# tissuetesterrev3.net
KiCad netlist of a schematic drawn in EAGLE
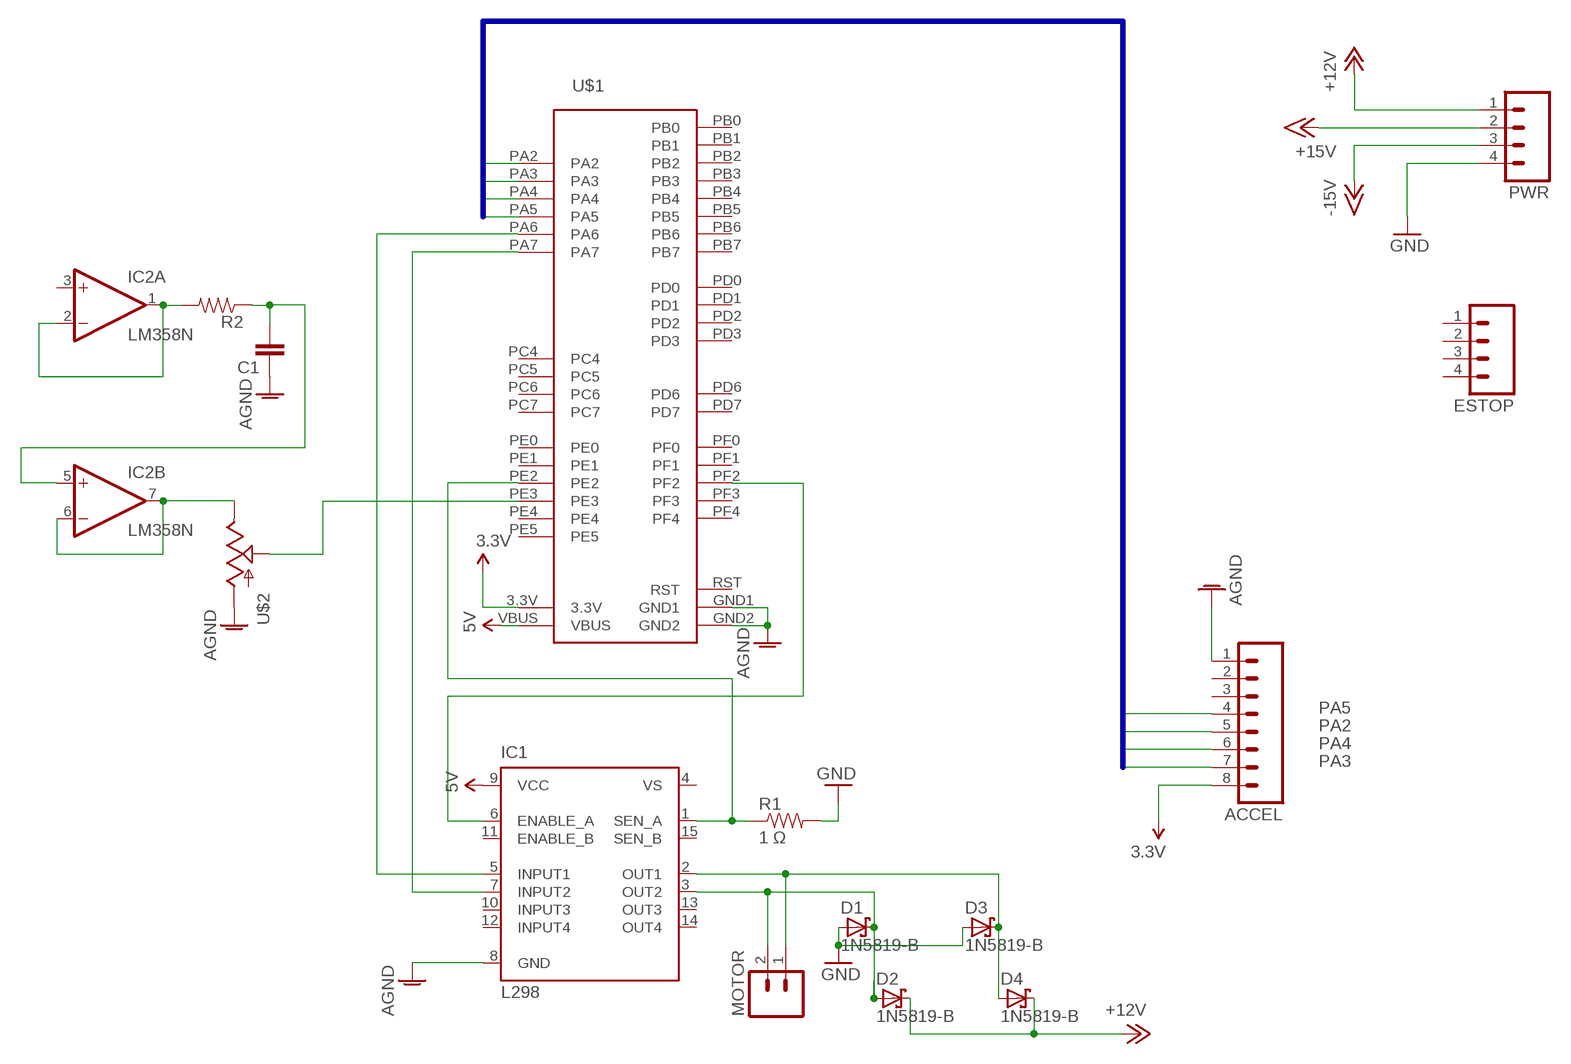
[diagram p0: schematic, sheet 1]

(export (version "E")
  (design (tool "Eeschema 10.0.6"))
  (components
    (comp (ref "ACCEL")
      (value "M08LOCK")
      (footprint "eagle-import:1X08_LOCK")
      (libsource (lib "eagle-import") (part "M08LOCK"))
    )
    (comp (ref "C1")
      (value "CAPKIT")
      (footprint "eagle-import:CAP-PTH-SMALL-KIT")
      (libsource (lib "eagle-import") (part "CAPKIT"))
    )
    (comp (ref "D1")
      (value "1N5819-B")
      (footprint "eagle-import:DO41-7.6")
      (libsource (lib "eagle-import") (part "1N5819-B"))
    )
    (comp (ref "D2")
      (value "1N5819-B")
      (footprint "eagle-import:DO41-7.6")
      (libsource (lib "eagle-import") (part "1N5819-B"))
    )
    (comp (ref "D3")
      (value "1N5819-B")
      (footprint "eagle-import:DO41-7.6")
      (libsource (lib "eagle-import") (part "1N5819-B"))
    )
    (comp (ref "D4")
      (value "1N5819-B")
      (footprint "eagle-import:DO41-7.6")
      (libsource (lib "eagle-import") (part "1N5819-B"))
    )
    (comp (ref "ESTOP")
      (value "M04LOCK")
      (footprint "eagle-import:1X04_LOCK")
      (libsource (lib "eagle-import") (part "M04LOCK"))
    )
    (comp (ref "IC1")
      (value "L298")
      (footprint "eagle-import:MULTIWATT-15")
      (fields (field (name "MPN") "L298N"))
      (libsource (lib "eagle-import") (part "L298"))
    )
    (comp (ref "IC2")
      (value "LM358N")
      (footprint "eagle-import:DIL08")
      (libsource (lib "eagle-import") (part "LM358N"))
    )
    (comp (ref "MOTOR")
      (value "M023.5MM")
      (footprint "eagle-import:SCREWTERMINAL-3.5MM-2")
      (libsource (lib "eagle-import") (part "M023.5MM"))
    )
    (comp (ref "PWR")
      (value "M04SCREW")
      (footprint "eagle-import:SCREWTERMINAL-3.5MM-4")
      (libsource (lib "eagle-import") (part "M04SCREW"))
    )
    (comp (ref "R1")
      (value "1 Ω")
      (footprint "eagle-import:AXIAL-0.6")
      (libsource (lib "eagle-import") (part "RESISTORPTH-1W"))
    )
    (comp (ref "R2")
      (value "RESISTORKIT")
      (footprint "eagle-import:AXIAL-0.3-KIT")
      (libsource (lib "eagle-import") (part "SparkFun-Resistors_RESISTORKIT"))
    )
    (comp (ref "U$1")
      (value "STELLARIS-LAUNCHPADSTELLARIS-LAUNCHPAD")
      (footprint "eagle-import:LAUNCHPAD-XL")
      (libsource (lib "eagle-import") (part "STELLARIS-LAUNCHPADSTELLARIS-LAUNCHPAD"))
    )
    (comp (ref "U$2")
      (value "POT")
      (footprint "eagle-import:ALPS_POT")
      (libsource (lib "eagle-import") (part "POT"))
    )
  )
  (nets
    (net (code "1") (name "+12V") (class "Default")
      (node (ref "D2") (pin "C") (pinfunction "C_C") (pintype "passive"))
      (node (ref "D4") (pin "C") (pinfunction "C_C") (pintype "passive"))
      (node (ref "PWR") (pin "1") (pinfunction "1_1") (pintype "passive"))
    )
    (net (code "2") (name "+15V") (class "Default")
      (node (ref "PWR") (pin "2") (pinfunction "2_2") (pintype "passive"))
    )
    (net (code "3") (name "-15V") (class "Default")
      (node (ref "PWR") (pin "3") (pinfunction "3_3") (pintype "passive"))
    )
    (net (code "4") (name "/PA2") (class "Default")
      (node (ref "ACCEL") (pin "5") (pinfunction "5_5") (pintype "passive"))
      (node (ref "U$1") (pin "PA2") (pinfunction "PA2_PA2") (pintype "bidirectional"))
    )
    (net (code "5") (name "/PA3") (class "Default")
      (node (ref "ACCEL") (pin "7") (pinfunction "7_7") (pintype "passive"))
      (node (ref "U$1") (pin "PA3") (pinfunction "PA3_PA3") (pintype "bidirectional"))
    )
    (net (code "6") (name "/PA4") (class "Default")
      (node (ref "ACCEL") (pin "6") (pinfunction "6_6") (pintype "passive"))
      (node (ref "U$1") (pin "PA4") (pinfunction "PA4_PA4") (pintype "bidirectional"))
    )
    (net (code "7") (name "/PA5") (class "Default")
      (node (ref "ACCEL") (pin "4") (pinfunction "4_4") (pintype "passive"))
      (node (ref "U$1") (pin "PA5") (pinfunction "PA5_PA5") (pintype "bidirectional"))
    )
    (net (code "8") (name "/RST") (class "Default")
      (node (ref "U$1") (pin "RST") (pinfunction "RST_RST") (pintype "power_in"))
    )
    (net (code "9") (name "/VS") (class "Default")
      (node (ref "IC1") (pin "4") (pinfunction "VS_4") (pintype "power_in"))
    )
    (net (code "10") (name "3.3V") (class "Default")
      (node (ref "ACCEL") (pin "8") (pinfunction "8_8") (pintype "passive"))
      (node (ref "U$1") (pin "3.3V") (pinfunction "3.3V_3.3V") (pintype "power_in"))
    )
    (net (code "11") (name "5V") (class "Default")
      (node (ref "IC1") (pin "9") (pinfunction "VCC_9") (pintype "power_in"))
      (node (ref "U$1") (pin "VBUS") (pinfunction "VBUS_VBUS") (pintype "power_in"))
    )
    (net (code "12") (name "AGND") (class "Default")
      (node (ref "ACCEL") (pin "1") (pinfunction "1_1") (pintype "passive"))
      (node (ref "C1") (pin "1") (pinfunction "1_1") (pintype "passive"))
      (node (ref "IC1") (pin "8") (pinfunction "GND_8") (pintype "power_in"))
      (node (ref "U$1") (pin "GND1") (pinfunction "GND1_GND1") (pintype "bidirectional"))
      (node (ref "U$1") (pin "GND2") (pinfunction "GND2_GND2") (pintype "power_in"))
      (node (ref "U$2") (pin "P$3") (pinfunction "A_P$3") (pintype "passive"))
    )
    (net (code "13") (name "GND") (class "Default")
      (node (ref "D1") (pin "A") (pinfunction "A_A") (pintype "passive"))
      (node (ref "D3") (pin "A") (pinfunction "A_A") (pintype "passive"))
      (node (ref "PWR") (pin "4") (pinfunction "4_4") (pintype "passive"))
      (node (ref "R1") (pin "P$2") (pinfunction "2_P$2") (pintype "passive"))
    )
    (net (code "14") (name "Net-(IC1-ENABLE_A)") (class "Default")
      (node (ref "IC1") (pin "6") (pinfunction "ENABLE_A_6") (pintype "input"))
      (node (ref "U$1") (pin "PF2") (pinfunction "PF2_PF2") (pintype "bidirectional"))
    )
    (net (code "15") (name "Net-(IC1-INPUT1)") (class "Default")
      (node (ref "IC1") (pin "5") (pinfunction "INPUT1_5") (pintype "input"))
      (node (ref "U$1") (pin "PA6") (pinfunction "PA6_PA6") (pintype "bidirectional"))
    )
    (net (code "16") (name "Net-(IC1-INPUT2)") (class "Default")
      (node (ref "IC1") (pin "7") (pinfunction "INPUT2_7") (pintype "input"))
      (node (ref "U$1") (pin "PA7") (pinfunction "PA7_PA7") (pintype "bidirectional"))
    )
    (net (code "17") (name "Net-(IC1-OUT1)") (class "Default")
      (node (ref "D3") (pin "C") (pinfunction "C_C") (pintype "passive"))
      (node (ref "D4") (pin "A") (pinfunction "A_A") (pintype "passive"))
      (node (ref "IC1") (pin "2") (pinfunction "OUT1_2") (pintype "output"))
      (node (ref "MOTOR") (pin "1") (pinfunction "1_1") (pintype "passive"))
    )
    (net (code "18") (name "Net-(IC1-OUT2)") (class "Default")
      (node (ref "D1") (pin "C") (pinfunction "C_C") (pintype "passive"))
      (node (ref "D2") (pin "A") (pinfunction "A_A") (pintype "passive"))
      (node (ref "IC1") (pin "3") (pinfunction "OUT2_3") (pintype "output"))
      (node (ref "MOTOR") (pin "2") (pinfunction "2_2") (pintype "passive"))
    )
    (net (code "19") (name "Net-(IC1-SEN_A)") (class "Default")
      (node (ref "IC1") (pin "1") (pinfunction "SEN_A_1") (pintype "input"))
      (node (ref "R1") (pin "P$1") (pinfunction "1_P$1") (pintype "passive"))
      (node (ref "U$1") (pin "PE2") (pinfunction "PE2_PE2") (pintype "bidirectional"))
    )
    (net (code "20") (name "Net-(IC2A--IN)") (class "Default")
      (node (ref "IC2") (pin "1") (pinfunction "OUT_1") (pintype "output"))
      (node (ref "IC2") (pin "2") (pinfunction "-IN_2") (pintype "input"))
      (node (ref "R2") (pin "P$2") (pinfunction "2_P$2") (pintype "passive"))
    )
    (net (code "21") (name "Net-(IC2B-+IN)") (class "Default")
      (node (ref "C1") (pin "2") (pinfunction "2_2") (pintype "passive"))
      (node (ref "IC2") (pin "5") (pinfunction "+IN_5") (pintype "input"))
      (node (ref "R2") (pin "P$1") (pinfunction "1_P$1") (pintype "passive"))
    )
    (net (code "22") (name "Net-(IC2B--IN)") (class "Default")
      (node (ref "IC2") (pin "6") (pinfunction "-IN_6") (pintype "input"))
      (node (ref "IC2") (pin "7") (pinfunction "OUT_7") (pintype "output"))
      (node (ref "U$2") (pin "P$1") (pinfunction "E_P$1") (pintype "passive"))
    )
    (net (code "23") (name "Net-(U$2-S)") (class "Default")
      (node (ref "U$1") (pin "PE3") (pinfunction "PE3_PE3") (pintype "bidirectional"))
      (node (ref "U$2") (pin "P$2") (pinfunction "S_P$2") (pintype "passive"))
    )
    (net (code "24") (name "unconnected-(ACCEL-Pad2)") (class "Default")
      (node (ref "ACCEL") (pin "2") (pinfunction "2_2") (pintype "passive"))
    )
    (net (code "25") (name "unconnected-(ACCEL-Pad3)") (class "Default")
      (node (ref "ACCEL") (pin "3") (pinfunction "3_3") (pintype "passive"))
    )
    (net (code "26") (name "unconnected-(ESTOP-Pad1)") (class "Default")
      (node (ref "ESTOP") (pin "1") (pinfunction "1_1") (pintype "passive"))
    )
    (net (code "27") (name "unconnected-(ESTOP-Pad2)") (class "Default")
      (node (ref "ESTOP") (pin "2") (pinfunction "2_2") (pintype "passive"))
    )
    (net (code "28") (name "unconnected-(ESTOP-Pad3)") (class "Default")
      (node (ref "ESTOP") (pin "3") (pinfunction "3_3") (pintype "passive"))
    )
    (net (code "29") (name "unconnected-(ESTOP-Pad4)") (class "Default")
      (node (ref "ESTOP") (pin "4") (pinfunction "4_4") (pintype "passive"))
    )
    (net (code "30") (name "unconnected-(IC1-ENABLE_B-Pad11)") (class "Default")
      (node (ref "IC1") (pin "11") (pinfunction "ENABLE_B_11") (pintype "input"))
    )
    (net (code "31") (name "unconnected-(IC1-INPUT3-Pad10)") (class "Default")
      (node (ref "IC1") (pin "10") (pinfunction "INPUT3_10") (pintype "input"))
    )
    (net (code "32") (name "unconnected-(IC1-INPUT4-Pad12)") (class "Default")
      (node (ref "IC1") (pin "12") (pinfunction "INPUT4_12") (pintype "input"))
    )
    (net (code "33") (name "unconnected-(IC1-OUT3-Pad13)") (class "Default")
      (node (ref "IC1") (pin "13") (pinfunction "OUT3_13") (pintype "output"))
    )
    (net (code "34") (name "unconnected-(IC1-OUT4-Pad14)") (class "Default")
      (node (ref "IC1") (pin "14") (pinfunction "OUT4_14") (pintype "output"))
    )
    (net (code "35") (name "unconnected-(IC1-SEN_B-Pad15)") (class "Default")
      (node (ref "IC1") (pin "15") (pinfunction "SEN_B_15") (pintype "input"))
    )
    (net (code "36") (name "unconnected-(IC2A-+IN-Pad3)") (class "Default")
      (node (ref "IC2") (pin "3") (pinfunction "+IN_3") (pintype "input"))
    )
    (net (code "37") (name "unconnected-(U$1-PadPB0)") (class "Default")
      (node (ref "U$1") (pin "PB0") (pinfunction "PB0_PB0") (pintype "bidirectional"))
    )
    (net (code "38") (name "unconnected-(U$1-PadPB1)") (class "Default")
      (node (ref "U$1") (pin "PB1") (pinfunction "PB1_PB1") (pintype "bidirectional"))
    )
    (net (code "39") (name "unconnected-(U$1-PadPB2)") (class "Default")
      (node (ref "U$1") (pin "PB2") (pinfunction "PB2_PB2") (pintype "bidirectional"))
    )
    (net (code "40") (name "unconnected-(U$1-PadPB3)") (class "Default")
      (node (ref "U$1") (pin "PB3") (pinfunction "PB3_PB3") (pintype "bidirectional"))
    )
    (net (code "41") (name "unconnected-(U$1-PadPB4)") (class "Default")
      (node (ref "U$1") (pin "PB4") (pinfunction "PB4_PB4") (pintype "bidirectional"))
    )
    (net (code "42") (name "unconnected-(U$1-PadPB5)") (class "Default")
      (node (ref "U$1") (pin "PB5") (pinfunction "PB5_PB5") (pintype "bidirectional"))
    )
    (net (code "43") (name "unconnected-(U$1-PadPB6)") (class "Default")
      (node (ref "U$1") (pin "PB6") (pinfunction "PB6_PB6") (pintype "bidirectional"))
    )
    (net (code "44") (name "unconnected-(U$1-PadPB7)") (class "Default")
      (node (ref "U$1") (pin "PB7") (pinfunction "PB7_PB7") (pintype "bidirectional"))
    )
    (net (code "45") (name "unconnected-(U$1-PadPC4)") (class "Default")
      (node (ref "U$1") (pin "PC4") (pinfunction "PC4_PC4") (pintype "bidirectional"))
    )
    (net (code "46") (name "unconnected-(U$1-PadPC5)") (class "Default")
      (node (ref "U$1") (pin "PC5") (pinfunction "PC5_PC5") (pintype "bidirectional"))
    )
    (net (code "47") (name "unconnected-(U$1-PadPC6)") (class "Default")
      (node (ref "U$1") (pin "PC6") (pinfunction "PC6_PC6") (pintype "bidirectional"))
    )
    (net (code "48") (name "unconnected-(U$1-PadPC7)") (class "Default")
      (node (ref "U$1") (pin "PC7") (pinfunction "PC7_PC7") (pintype "bidirectional"))
    )
    (net (code "49") (name "unconnected-(U$1-PadPD0)") (class "Default")
      (node (ref "U$1") (pin "PD0") (pinfunction "PD0_PD0") (pintype "bidirectional"))
    )
    (net (code "50") (name "unconnected-(U$1-PadPD1)") (class "Default")
      (node (ref "U$1") (pin "PD1") (pinfunction "PD1_PD1") (pintype "bidirectional"))
    )
    (net (code "51") (name "unconnected-(U$1-PadPD2)") (class "Default")
      (node (ref "U$1") (pin "PD2") (pinfunction "PD2_PD2") (pintype "bidirectional"))
    )
    (net (code "52") (name "unconnected-(U$1-PadPD3)") (class "Default")
      (node (ref "U$1") (pin "PD3") (pinfunction "PD3_PD3") (pintype "bidirectional"))
    )
    (net (code "53") (name "unconnected-(U$1-PadPD6)") (class "Default")
      (node (ref "U$1") (pin "PD6") (pinfunction "PD6_PD6") (pintype "bidirectional"))
    )
    (net (code "54") (name "unconnected-(U$1-PadPD7)") (class "Default")
      (node (ref "U$1") (pin "PD7") (pinfunction "PD7_PD7") (pintype "bidirectional"))
    )
    (net (code "55") (name "unconnected-(U$1-PadPE0)") (class "Default")
      (node (ref "U$1") (pin "PE0") (pinfunction "PE0_PE0") (pintype "bidirectional"))
    )
    (net (code "56") (name "unconnected-(U$1-PadPE1)") (class "Default")
      (node (ref "U$1") (pin "PE1") (pinfunction "PE1_PE1") (pintype "bidirectional"))
    )
    (net (code "57") (name "unconnected-(U$1-PadPE4)") (class "Default")
      (node (ref "U$1") (pin "PE4") (pinfunction "PE4_PE4") (pintype "bidirectional"))
    )
    (net (code "58") (name "unconnected-(U$1-PadPE5)") (class "Default")
      (node (ref "U$1") (pin "PE5") (pinfunction "PE5_PE5") (pintype "bidirectional"))
    )
    (net (code "59") (name "unconnected-(U$1-PadPF0)") (class "Default")
      (node (ref "U$1") (pin "PF0") (pinfunction "PF0_PF0") (pintype "bidirectional"))
    )
    (net (code "60") (name "unconnected-(U$1-PadPF1)") (class "Default")
      (node (ref "U$1") (pin "PF1") (pinfunction "PF1_PF1") (pintype "bidirectional"))
    )
    (net (code "61") (name "unconnected-(U$1-PadPF3)") (class "Default")
      (node (ref "U$1") (pin "PF3") (pinfunction "PF3_PF3") (pintype "bidirectional"))
    )
    (net (code "62") (name "unconnected-(U$1-PadPF4)") (class "Default")
      (node (ref "U$1") (pin "PF4") (pinfunction "PF4_PF4") (pintype "bidirectional"))
    )
  )
)
